# TEENSY_2_1.net
KiCad netlist of a schematic drawn in Altium Designer
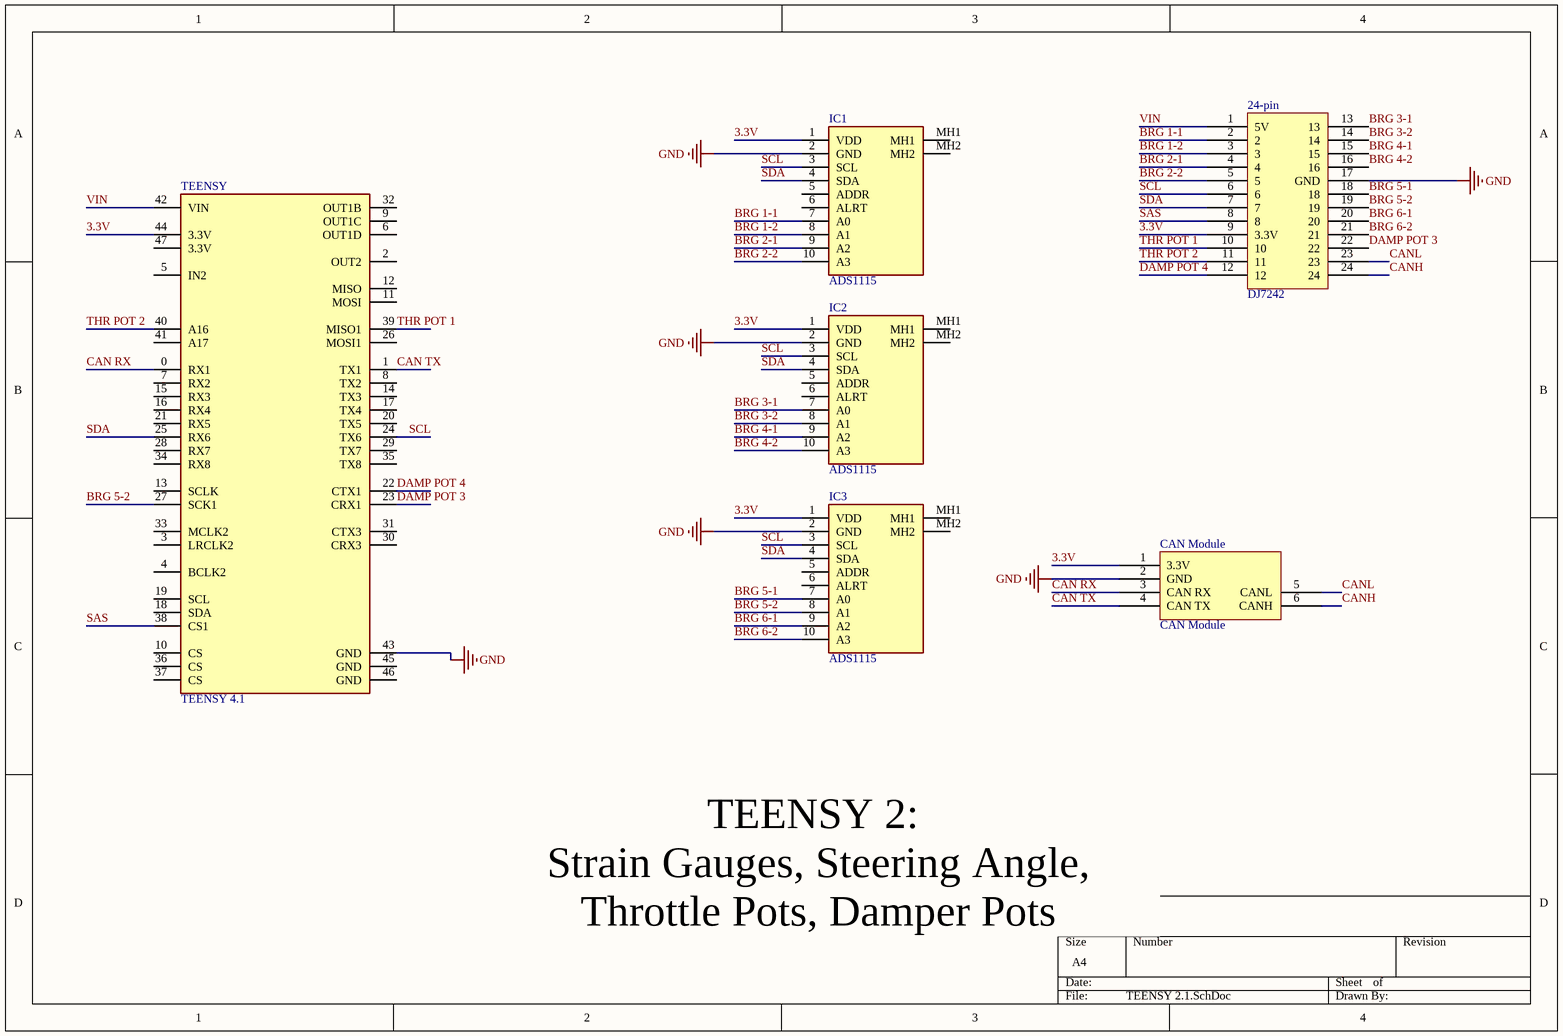
[diagram p0: TEENSY 2.1.SchDoc]

(export (version "E")
  (design (tool "Eeschema 10.0.6"))
  (components
    (comp (ref "24-pin")
      (value "DJ7242")
      (footprint "DJ7242-Footprint-1")
      (description "24-pin connector")
      (libsource (lib "cmabey15") (part "DJ7242-Symbol-1"))
    )
    (comp (ref "CAN Module")
      (value "CAN Module")
      (footprint "CAN Module-Footprint-1")
      (description "CAN waveshare")
      (libsource (lib "cmabey15") (part "CAN Module-Symbol-1"))
    )
    (comp (ref "IC1")
      (value "ADS1115")
      (footprint "SamacSys:ADS1115")
      (description "Integrated Circuit")
      (libsource (lib "*") (part "ADS1115"))
    )
    (comp (ref "IC2")
      (value "ADS1115")
      (footprint "SamacSys:ADS1115")
      (description "Integrated Circuit")
      (libsource (lib "*") (part "ADS1115"))
    )
    (comp (ref "IC3")
      (value "ADS1115")
      (footprint "SamacSys:ADS1115")
      (description "Integrated Circuit")
      (libsource (lib "*") (part "ADS1115"))
    )
    (comp (ref "TEENSY")
      (value "TEENSY 4.1")
      (footprint "FP-DEV-16996-MFG")
      (description "TEENSY 4.1 (HEADERS)")
      (libsource (lib "Altium Content Vault") (part "080115a1ce54750370cf87ec145ee29"))
    )
  )
  (nets
    (net (code "1") (name "/3.3V") (class "Default")
      (node (ref "24-pin") (pin "9") (pinfunction "3.3V_9") (pintype "passive"))
      (node (ref "CAN Module") (pin "1") (pinfunction "3.3V_1") (pintype "passive"))
      (node (ref "IC1") (pin "1") (pinfunction "VDD_1") (pintype "passive"))
      (node (ref "IC2") (pin "1") (pinfunction "VDD_1") (pintype "passive"))
      (node (ref "IC3") (pin "1") (pinfunction "VDD_1") (pintype "passive"))
      (node (ref "TEENSY") (pin "44") (pinfunction "3.3V_44") (pintype "passive"))
    )
    (net (code "2") (name "/BRG 1-1") (class "Default")
      (node (ref "24-pin") (pin "2") (pinfunction "2_2") (pintype "passive"))
      (node (ref "IC1") (pin "7") (pinfunction "A0_7") (pintype "passive"))
    )
    (net (code "3") (name "/BRG 1-2") (class "Default")
      (node (ref "24-pin") (pin "3") (pinfunction "3_3") (pintype "passive"))
      (node (ref "IC1") (pin "8") (pinfunction "A1_8") (pintype "passive"))
    )
    (net (code "4") (name "/BRG 2-1") (class "Default")
      (node (ref "24-pin") (pin "4") (pinfunction "4_4") (pintype "passive"))
      (node (ref "IC1") (pin "9") (pinfunction "A2_9") (pintype "passive"))
    )
    (net (code "5") (name "/BRG 2-2") (class "Default")
      (node (ref "24-pin") (pin "5") (pinfunction "5_5") (pintype "passive"))
      (node (ref "IC1") (pin "10") (pinfunction "A3_10") (pintype "passive"))
    )
    (net (code "6") (name "/BRG 3-1") (class "Default")
      (node (ref "24-pin") (pin "13") (pinfunction "13_13") (pintype "passive"))
      (node (ref "IC2") (pin "7") (pinfunction "A0_7") (pintype "passive"))
    )
    (net (code "7") (name "/BRG 3-2") (class "Default")
      (node (ref "24-pin") (pin "14") (pinfunction "14_14") (pintype "passive"))
      (node (ref "IC2") (pin "8") (pinfunction "A1_8") (pintype "passive"))
    )
    (net (code "8") (name "/BRG 4-1") (class "Default")
      (node (ref "24-pin") (pin "15") (pinfunction "15_15") (pintype "passive"))
      (node (ref "IC2") (pin "9") (pinfunction "A2_9") (pintype "passive"))
    )
    (net (code "9") (name "/BRG 4-2") (class "Default")
      (node (ref "24-pin") (pin "16") (pinfunction "16_16") (pintype "passive"))
      (node (ref "IC2") (pin "10") (pinfunction "A3_10") (pintype "passive"))
    )
    (net (code "10") (name "/BRG 5-1") (class "Default")
      (node (ref "24-pin") (pin "18") (pinfunction "18_18") (pintype "passive"))
      (node (ref "IC3") (pin "7") (pinfunction "A0_7") (pintype "passive"))
    )
    (net (code "11") (name "/BRG 5-2") (class "Default")
      (node (ref "24-pin") (pin "19") (pinfunction "19_19") (pintype "passive"))
      (node (ref "IC3") (pin "8") (pinfunction "A1_8") (pintype "passive"))
      (node (ref "TEENSY") (pin "27") (pinfunction "SCK1_27") (pintype "passive"))
    )
    (net (code "12") (name "/BRG 6-1") (class "Default")
      (node (ref "24-pin") (pin "20") (pinfunction "20_20") (pintype "passive"))
      (node (ref "IC3") (pin "9") (pinfunction "A2_9") (pintype "passive"))
    )
    (net (code "13") (name "/BRG 6-2") (class "Default")
      (node (ref "24-pin") (pin "21") (pinfunction "21_21") (pintype "passive"))
      (node (ref "IC3") (pin "10") (pinfunction "A3_10") (pintype "passive"))
    )
    (net (code "14") (name "/CAN RX") (class "Default")
      (node (ref "CAN Module") (pin "3") (pinfunction "CAN_RX_3") (pintype "passive"))
      (node (ref "TEENSY") (pin "0") (pinfunction "RX1_0") (pintype "passive"))
    )
    (net (code "15") (name "/CAN TX") (class "Default")
      (node (ref "CAN Module") (pin "4") (pinfunction "CAN_TX_4") (pintype "passive"))
      (node (ref "TEENSY") (pin "1") (pinfunction "TX1_1") (pintype "passive"))
    )
    (net (code "16") (name "/CANH") (class "Default")
      (node (ref "24-pin") (pin "24") (pinfunction "24_24") (pintype "passive"))
      (node (ref "CAN Module") (pin "6") (pinfunction "CANH_6") (pintype "passive"))
    )
    (net (code "17") (name "/CANL") (class "Default")
      (node (ref "24-pin") (pin "23") (pinfunction "23_23") (pintype "passive"))
      (node (ref "CAN Module") (pin "5") (pinfunction "CANL_5") (pintype "passive"))
    )
    (net (code "18") (name "/DAMP POT 3") (class "Default")
      (node (ref "24-pin") (pin "22") (pinfunction "22_22") (pintype "passive"))
      (node (ref "TEENSY") (pin "23") (pinfunction "CRX1_23") (pintype "passive"))
    )
    (net (code "19") (name "/DAMP POT 4") (class "Default")
      (node (ref "24-pin") (pin "12") (pinfunction "12_12") (pintype "passive"))
      (node (ref "TEENSY") (pin "22") (pinfunction "CTX1_22") (pintype "passive"))
    )
    (net (code "20") (name "/SAS") (class "Default")
      (node (ref "24-pin") (pin "8") (pinfunction "8_8") (pintype "passive"))
      (node (ref "TEENSY") (pin "38") (pinfunction "CS1_38") (pintype "passive"))
    )
    (net (code "21") (name "/SCL") (class "Default")
      (node (ref "24-pin") (pin "6") (pinfunction "6_6") (pintype "passive"))
      (node (ref "IC1") (pin "3") (pinfunction "SCL_3") (pintype "passive"))
      (node (ref "IC2") (pin "3") (pinfunction "SCL_3") (pintype "passive"))
      (node (ref "IC3") (pin "3") (pinfunction "SCL_3") (pintype "passive"))
      (node (ref "TEENSY") (pin "24") (pinfunction "TX6_24") (pintype "passive"))
    )
    (net (code "22") (name "/SDA") (class "Default")
      (node (ref "24-pin") (pin "7") (pinfunction "7_7") (pintype "passive"))
      (node (ref "IC1") (pin "4") (pinfunction "SDA_4") (pintype "passive"))
      (node (ref "IC2") (pin "4") (pinfunction "SDA_4") (pintype "passive"))
      (node (ref "IC3") (pin "4") (pinfunction "SDA_4") (pintype "passive"))
      (node (ref "TEENSY") (pin "25") (pinfunction "RX6_25") (pintype "passive"))
    )
    (net (code "23") (name "/THR POT 1") (class "Default")
      (node (ref "24-pin") (pin "10") (pinfunction "10_10") (pintype "passive"))
      (node (ref "TEENSY") (pin "39") (pinfunction "MISO1_39") (pintype "passive"))
    )
    (net (code "24") (name "/THR POT 2") (class "Default")
      (node (ref "24-pin") (pin "11") (pinfunction "11_11") (pintype "passive"))
      (node (ref "TEENSY") (pin "40") (pinfunction "A16_40") (pintype "passive"))
    )
    (net (code "25") (name "/VIN") (class "Default")
      (node (ref "24-pin") (pin "1") (pinfunction "5V_1") (pintype "passive"))
      (node (ref "TEENSY") (pin "42") (pinfunction "VIN_42") (pintype "passive"))
    )
    (net (code "26") (name "GND") (class "Default")
      (node (ref "24-pin") (pin "17") (pinfunction "GND_17") (pintype "passive"))
      (node (ref "CAN Module") (pin "2") (pinfunction "GND_2") (pintype "passive"))
      (node (ref "IC1") (pin "2") (pinfunction "GND_2") (pintype "passive"))
      (node (ref "IC2") (pin "2") (pinfunction "GND_2") (pintype "passive"))
      (node (ref "IC3") (pin "2") (pinfunction "GND_2") (pintype "passive"))
      (node (ref "TEENSY") (pin "43") (pinfunction "GND_43") (pintype "passive"))
    )
    (net (code "27") (name "unconnected-(IC1-ADDR-Pad5)") (class "Default")
      (node (ref "IC1") (pin "5") (pinfunction "ADDR_5") (pintype "passive"))
    )
    (net (code "28") (name "unconnected-(IC1-ALRT-Pad6)") (class "Default")
      (node (ref "IC1") (pin "6") (pinfunction "ALRT_6") (pintype "passive"))
    )
    (net (code "29") (name "unconnected-(IC1-PadMH1)") (class "Default")
      (node (ref "IC1") (pin "MH1") (pinfunction "MH1_MH1") (pintype "passive"))
    )
    (net (code "30") (name "unconnected-(IC1-PadMH2)") (class "Default")
      (node (ref "IC1") (pin "MH2") (pinfunction "MH2_MH2") (pintype "passive"))
    )
    (net (code "31") (name "unconnected-(IC2-ADDR-Pad5)") (class "Default")
      (node (ref "IC2") (pin "5") (pinfunction "ADDR_5") (pintype "passive"))
    )
    (net (code "32") (name "unconnected-(IC2-ALRT-Pad6)") (class "Default")
      (node (ref "IC2") (pin "6") (pinfunction "ALRT_6") (pintype "passive"))
    )
    (net (code "33") (name "unconnected-(IC2-PadMH1)") (class "Default")
      (node (ref "IC2") (pin "MH1") (pinfunction "MH1_MH1") (pintype "passive"))
    )
    (net (code "34") (name "unconnected-(IC2-PadMH2)") (class "Default")
      (node (ref "IC2") (pin "MH2") (pinfunction "MH2_MH2") (pintype "passive"))
    )
    (net (code "35") (name "unconnected-(IC3-ADDR-Pad5)") (class "Default")
      (node (ref "IC3") (pin "5") (pinfunction "ADDR_5") (pintype "passive"))
    )
    (net (code "36") (name "unconnected-(IC3-ALRT-Pad6)") (class "Default")
      (node (ref "IC3") (pin "6") (pinfunction "ALRT_6") (pintype "passive"))
    )
    (net (code "37") (name "unconnected-(IC3-PadMH1)") (class "Default")
      (node (ref "IC3") (pin "MH1") (pinfunction "MH1_MH1") (pintype "passive"))
    )
    (net (code "38") (name "unconnected-(IC3-PadMH2)") (class "Default")
      (node (ref "IC3") (pin "MH2") (pinfunction "MH2_MH2") (pintype "passive"))
    )
    (net (code "39") (name "unconnected-(TEENSY-3.3V-Pad47)") (class "Default")
      (node (ref "TEENSY") (pin "47") (pinfunction "3.3V_47") (pintype "passive"))
    )
    (net (code "40") (name "unconnected-(TEENSY-A17-Pad41)") (class "Default")
      (node (ref "TEENSY") (pin "41") (pinfunction "A17_41") (pintype "passive"))
    )
    (net (code "41") (name "unconnected-(TEENSY-BCLK2-Pad4)") (class "Default")
      (node (ref "TEENSY") (pin "4") (pinfunction "BCLK2_4") (pintype "passive"))
    )
    (net (code "42") (name "unconnected-(TEENSY-CRX3-Pad30)") (class "Default")
      (node (ref "TEENSY") (pin "30") (pinfunction "CRX3_30") (pintype "passive"))
    )
    (net (code "43") (name "unconnected-(TEENSY-CS-Pad10)") (class "Default")
      (node (ref "TEENSY") (pin "10") (pinfunction "CS_10") (pintype "passive"))
    )
    (net (code "44") (name "unconnected-(TEENSY-CS-Pad36)") (class "Default")
      (node (ref "TEENSY") (pin "36") (pinfunction "CS_36") (pintype "passive"))
    )
    (net (code "45") (name "unconnected-(TEENSY-CS-Pad37)") (class "Default")
      (node (ref "TEENSY") (pin "37") (pinfunction "CS_37") (pintype "passive"))
    )
    (net (code "46") (name "unconnected-(TEENSY-CTX3-Pad31)") (class "Default")
      (node (ref "TEENSY") (pin "31") (pinfunction "CTX3_31") (pintype "passive"))
    )
    (net (code "47") (name "unconnected-(TEENSY-GND-Pad45)") (class "Default")
      (node (ref "TEENSY") (pin "45") (pinfunction "GND_45") (pintype "passive"))
    )
    (net (code "48") (name "unconnected-(TEENSY-GND-Pad46)") (class "Default")
      (node (ref "TEENSY") (pin "46") (pinfunction "GND_46") (pintype "passive"))
    )
    (net (code "49") (name "unconnected-(TEENSY-IN2-Pad5)") (class "Default")
      (node (ref "TEENSY") (pin "5") (pinfunction "IN2_5") (pintype "passive"))
    )
    (net (code "50") (name "unconnected-(TEENSY-LRCLK2-Pad3)") (class "Default")
      (node (ref "TEENSY") (pin "3") (pinfunction "LRCLK2_3") (pintype "passive"))
    )
    (net (code "51") (name "unconnected-(TEENSY-MCLK2-Pad33)") (class "Default")
      (node (ref "TEENSY") (pin "33") (pinfunction "MCLK2_33") (pintype "passive"))
    )
    (net (code "52") (name "unconnected-(TEENSY-MISO-Pad12)") (class "Default")
      (node (ref "TEENSY") (pin "12") (pinfunction "MISO_12") (pintype "passive"))
    )
    (net (code "53") (name "unconnected-(TEENSY-MOSI-Pad11)") (class "Default")
      (node (ref "TEENSY") (pin "11") (pinfunction "MOSI_11") (pintype "passive"))
    )
    (net (code "54") (name "unconnected-(TEENSY-MOSI1-Pad26)") (class "Default")
      (node (ref "TEENSY") (pin "26") (pinfunction "MOSI1_26") (pintype "passive"))
    )
    (net (code "55") (name "unconnected-(TEENSY-OUT1B-Pad32)") (class "Default")
      (node (ref "TEENSY") (pin "32") (pinfunction "OUT1B_32") (pintype "passive"))
    )
    (net (code "56") (name "unconnected-(TEENSY-OUT1C-Pad9)") (class "Default")
      (node (ref "TEENSY") (pin "9") (pinfunction "OUT1C_9") (pintype "passive"))
    )
    (net (code "57") (name "unconnected-(TEENSY-OUT1D-Pad6)") (class "Default")
      (node (ref "TEENSY") (pin "6") (pinfunction "OUT1D_6") (pintype "passive"))
    )
    (net (code "58") (name "unconnected-(TEENSY-OUT2-Pad2)") (class "Default")
      (node (ref "TEENSY") (pin "2") (pinfunction "OUT2_2") (pintype "passive"))
    )
    (net (code "59") (name "unconnected-(TEENSY-RX2-Pad7)") (class "Default")
      (node (ref "TEENSY") (pin "7") (pinfunction "RX2_7") (pintype "passive"))
    )
    (net (code "60") (name "unconnected-(TEENSY-RX3-Pad15)") (class "Default")
      (node (ref "TEENSY") (pin "15") (pinfunction "RX3_15") (pintype "passive"))
    )
    (net (code "61") (name "unconnected-(TEENSY-RX4-Pad16)") (class "Default")
      (node (ref "TEENSY") (pin "16") (pinfunction "RX4_16") (pintype "passive"))
    )
    (net (code "62") (name "unconnected-(TEENSY-RX5-Pad21)") (class "Default")
      (node (ref "TEENSY") (pin "21") (pinfunction "RX5_21") (pintype "passive"))
    )
    (net (code "63") (name "unconnected-(TEENSY-RX7-Pad28)") (class "Default")
      (node (ref "TEENSY") (pin "28") (pinfunction "RX7_28") (pintype "passive"))
    )
    (net (code "64") (name "unconnected-(TEENSY-RX8-Pad34)") (class "Default")
      (node (ref "TEENSY") (pin "34") (pinfunction "RX8_34") (pintype "passive"))
    )
    (net (code "65") (name "unconnected-(TEENSY-SCL-Pad19)") (class "Default")
      (node (ref "TEENSY") (pin "19") (pinfunction "SCL_19") (pintype "passive"))
    )
    (net (code "66") (name "unconnected-(TEENSY-SCLK-Pad13)") (class "Default")
      (node (ref "TEENSY") (pin "13") (pinfunction "SCLK_13") (pintype "passive"))
    )
    (net (code "67") (name "unconnected-(TEENSY-SDA-Pad18)") (class "Default")
      (node (ref "TEENSY") (pin "18") (pinfunction "SDA_18") (pintype "passive"))
    )
    (net (code "68") (name "unconnected-(TEENSY-TX2-Pad8)") (class "Default")
      (node (ref "TEENSY") (pin "8") (pinfunction "TX2_8") (pintype "passive"))
    )
    (net (code "69") (name "unconnected-(TEENSY-TX3-Pad14)") (class "Default")
      (node (ref "TEENSY") (pin "14") (pinfunction "TX3_14") (pintype "passive"))
    )
    (net (code "70") (name "unconnected-(TEENSY-TX4-Pad17)") (class "Default")
      (node (ref "TEENSY") (pin "17") (pinfunction "TX4_17") (pintype "passive"))
    )
    (net (code "71") (name "unconnected-(TEENSY-TX5-Pad20)") (class "Default")
      (node (ref "TEENSY") (pin "20") (pinfunction "TX5_20") (pintype "passive"))
    )
    (net (code "72") (name "unconnected-(TEENSY-TX7-Pad29)") (class "Default")
      (node (ref "TEENSY") (pin "29") (pinfunction "TX7_29") (pintype "passive"))
    )
    (net (code "73") (name "unconnected-(TEENSY-TX8-Pad35)") (class "Default")
      (node (ref "TEENSY") (pin "35") (pinfunction "TX8_35") (pintype "passive"))
    )
  )
)
